# 02_ESP8266.net
KiCad netlist of a schematic drawn in Altium Designer
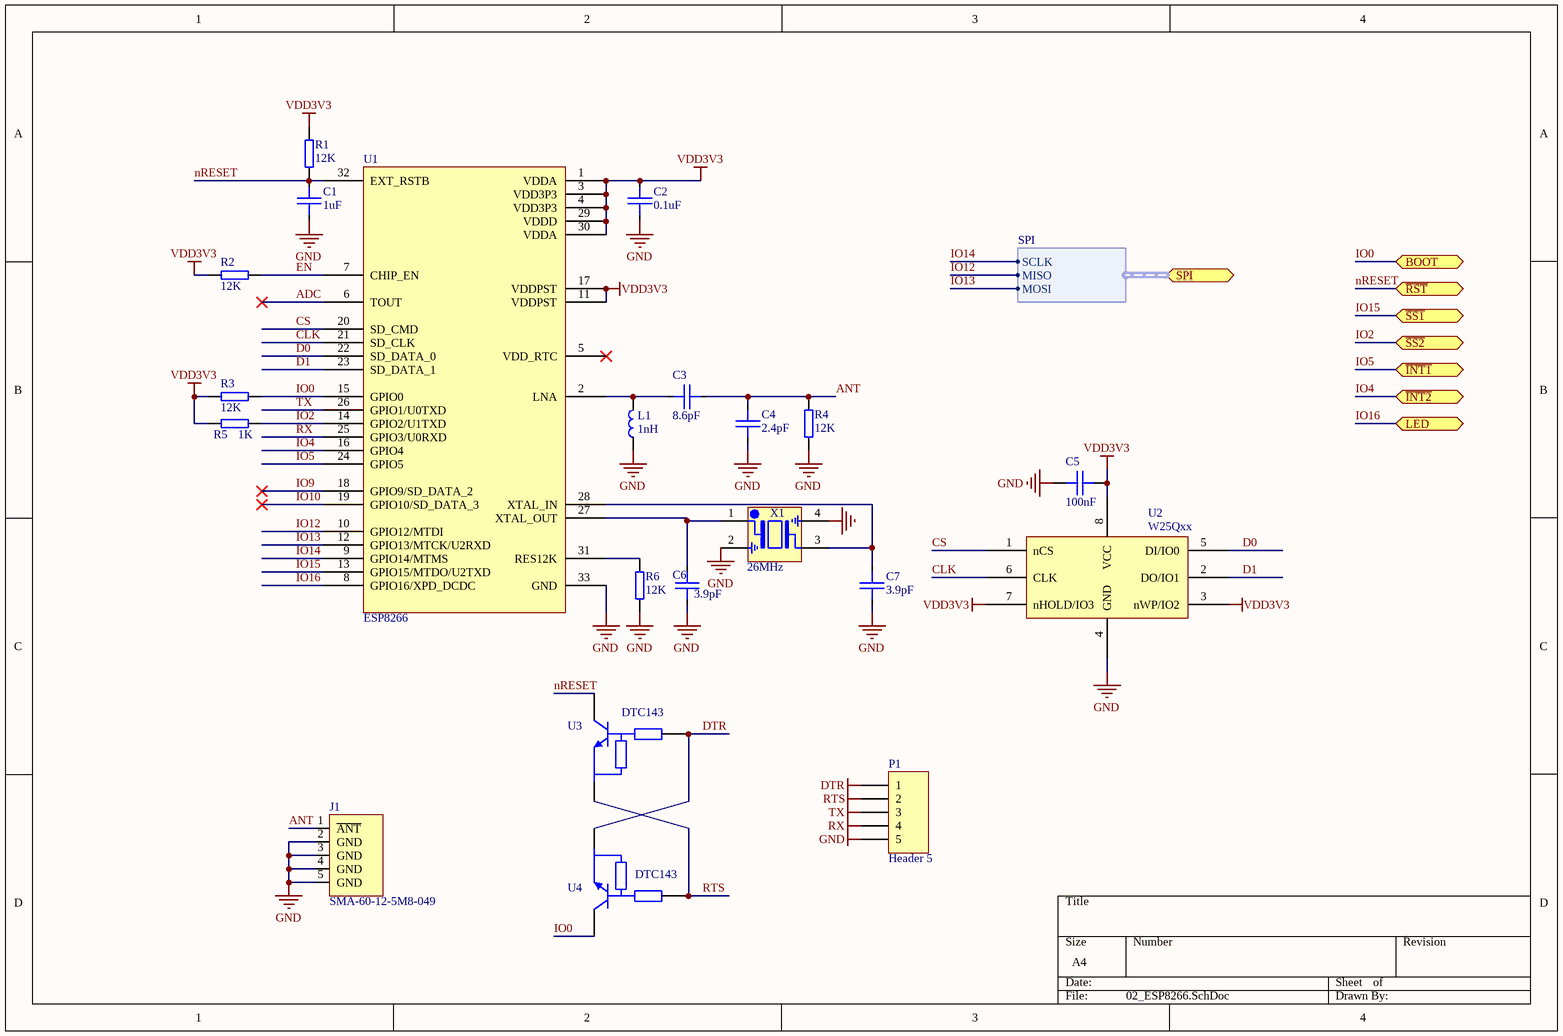
[diagram p0: 02_ESP8266.SchDoc]

(export (version "E")
  (design (tool "Eeschema 10.0.6"))
  (components
    (comp (ref "C1")
      (value "1uF")
      (footprint "SMT_C_0402")
      (description "Surface mount capacitor 0402")
      (libsource (lib "Vowstar_Basic_Device") (part "SMT_C_0402_1"))
    )
    (comp (ref "C2")
      (value "0.1uF")
      (footprint "SMT_C_0402")
      (description "Surface mount capacitor 0402")
      (libsource (lib "Vowstar_Basic_Device") (part "SMT_C_0402_1"))
    )
    (comp (ref "C3")
      (value "8.6pF")
      (footprint "SMT_C_0402")
      (description "Surface mount capacitor 0402")
      (libsource (lib "Vowstar_Basic_Device") (part "SMT_C_0402_1"))
    )
    (comp (ref "C4")
      (value "2.4pF")
      (footprint "SMT_C_0402")
      (description "Surface mount capacitor 0402")
      (libsource (lib "Vowstar_Basic_Device") (part "SMT_C_0402_1"))
    )
    (comp (ref "C5")
      (value "100nF")
      (footprint "SMT_C_0402")
      (description "Surface mount capacitor 0402")
      (libsource (lib "Vowstar_Basic_Device") (part "SMT_C_0402"))
    )
    (comp (ref "C6")
      (value "3.9pF")
      (footprint "SMT_C_0402")
      (description "Surface mount capacitor 0402")
      (libsource (lib "Vowstar_Basic_Device") (part "SMT_C_0402_1"))
    )
    (comp (ref "C7")
      (value "3.9pF")
      (footprint "SMT_C_0402")
      (description "Surface mount capacitor 0402")
      (libsource (lib "Vowstar_Basic_Device") (part "SMT_C_0402_1"))
    )
    (comp (ref "J1")
      (value "SMA-60-12-5M8-049")
      (footprint "SMA-60-12-5M8-049")
      (description "sma 60-12-5M8-049")
      (libsource (lib "Vowstar_Connector") (part "SMA-60-12-5M8-049"))
    )
    (comp (ref "L1")
      (value "1nH")
      (footprint "SMT_L_0402")
      (description "Surface mount inductor 0402")
      (libsource (lib "Vowstar_Basic_Device") (part "SMT_L_0402"))
    )
    (comp (ref "P1")
      (value "Header 5")
      (footprint "HDR1X5")
      (description "Header, 5-Pin")
      (fields (field (name "PUBLISHER") "Altium Limited"))
      (libsource (lib "Miscellaneous Connectors") (part "Header 5"))
    )
    (comp (ref "R1")
      (value "12K")
      (footprint "SMT_R_0402")
      (description "Surface mount resistor 0402")
      (libsource (lib "Vowstar_Basic_Device") (part "SMT_R_0402"))
    )
    (comp (ref "R2")
      (value "12K")
      (footprint "SMT_R_0402")
      (description "Surface mount resistor 0402")
      (libsource (lib "Vowstar_Basic_Device") (part "SMT_R_0402"))
    )
    (comp (ref "R3")
      (value "12K")
      (footprint "SMT_R_0402")
      (description "Surface mount resistor 0402")
      (libsource (lib "Vowstar_Basic_Device") (part "SMT_R_0402"))
    )
    (comp (ref "R4")
      (value "12K")
      (footprint "SMT_R_0402")
      (description "Surface mount resistor 0402")
      (libsource (lib "Vowstar_Basic_Device") (part "SMT_R_0402"))
    )
    (comp (ref "R5")
      (value "1K")
      (footprint "SMT_R_0402")
      (description "Surface mount resistor 0402")
      (libsource (lib "Vowstar_Basic_Device") (part "SMT_R_0402"))
    )
    (comp (ref "R6")
      (value "12K")
      (footprint "SMT_R_0402")
      (description "Surface mount resistor 0402")
      (libsource (lib "Vowstar_Basic_Device") (part "SMT_R_0402"))
    )
    (comp (ref "U1") (value "ESP8266") (footprint "QFN32") (libsource (lib "Vowstar_MCU") (part "ESP8266")))
    (comp (ref "U2")
      (value "W25Qxx")
      (footprint "SOP-8")
      (description "Serial flash memory with dual and quad SPI")
      (libsource (lib "Vowstar_IC_General") (part "W25Qxx"))
    )
    (comp (ref "U3")
      (value "DTC143")
      (footprint "SOT23-3")
      (description "Digital transistors (built-in resistors)")
      (libsource (lib "Vowstar_IC_General") (part "DTC143"))
    )
    (comp (ref "U4")
      (value "DTC143")
      (footprint "SOT23-3")
      (description "Digital transistors (built-in resistors)")
      (libsource (lib "Vowstar_IC_General") (part "DTC143"))
    )
    (comp (ref "X1")
      (value "26MHz")
      (footprint "SMT_XTAL_3225")
      (description "Passive crystal")
      (libsource (lib "Vowstar_Basic_Device") (part "SMT_XTAL_PASSIVE"))
    )
  )
  (nets
    (net (code "2") (name "/ADC") (class "Default")
      (node (ref "U1") (pin "6") (pinfunction "TOUT_6") (pintype "tri_state+no_connect"))
    )
    (net (code "3") (name "/ANT") (class "Default")
      (node (ref "C3") (pin "1") (pinfunction "1_1") (pintype "passive"))
      (node (ref "C4") (pin "1") (pinfunction "1_1") (pintype "passive"))
      (node (ref "J1") (pin "1") (pinfunction "~{ANT}_1") (pintype "passive"))
      (node (ref "R4") (pin "2") (pinfunction "2_2") (pintype "passive"))
    )
    (net (code "4") (name "/CLK") (class "Default")
      (node (ref "U1") (pin "21") (pinfunction "SD_CLK_21") (pintype "passive"))
      (node (ref "U2") (pin "6") (pinfunction "CLK_6") (pintype "passive"))
    )
    (net (code "5") (name "/CS") (class "Default")
      (node (ref "U1") (pin "20") (pinfunction "SD_CMD_20") (pintype "passive"))
      (node (ref "U2") (pin "1") (pinfunction "nCS_1") (pintype "passive"))
    )
    (net (code "6") (name "/D0") (class "Default")
      (node (ref "U1") (pin "22") (pinfunction "SD_DATA_0_22") (pintype "passive"))
      (node (ref "U2") (pin "5") (pinfunction "DI/IO0_5") (pintype "passive"))
    )
    (net (code "7") (name "/D1") (class "Default")
      (node (ref "U1") (pin "23") (pinfunction "SD_DATA_1_23") (pintype "passive"))
      (node (ref "U2") (pin "2") (pinfunction "DO/IO1_2") (pintype "passive"))
    )
    (net (code "8") (name "/EN") (class "Default")
      (node (ref "R2") (pin "1") (pinfunction "1_1") (pintype "passive"))
      (node (ref "U1") (pin "7") (pinfunction "CHIP_EN_7") (pintype "tri_state"))
    )
    (net (code "9") (name "/IO0") (class "Default")
      (node (ref "R3") (pin "1") (pinfunction "1_1") (pintype "passive"))
      (node (ref "U1") (pin "15") (pinfunction "GPIO0_15") (pintype "passive"))
      (node (ref "U4") (pin "3") (pinfunction "C_3") (pintype "passive"))
    )
    (net (code "10") (name "/IO2") (class "Default")
      (node (ref "R5") (pin "1") (pinfunction "1_1") (pintype "passive"))
      (node (ref "U1") (pin "14") (pinfunction "GPIO2/U1TXD_14") (pintype "passive"))
    )
    (net (code "11") (name "/IO4") (class "Default")
      (node (ref "U1") (pin "16") (pinfunction "GPIO4_16") (pintype "passive"))
    )
    (net (code "12") (name "/IO5") (class "Default")
      (node (ref "U1") (pin "24") (pinfunction "GPIO5_24") (pintype "passive"))
    )
    (net (code "13") (name "/IO9") (class "Default")
      (node (ref "U1") (pin "18") (pinfunction "GPIO9/SD_DATA_2_18") (pintype "passive+no_connect"))
    )
    (net (code "14") (name "/IO10") (class "Default")
      (node (ref "U1") (pin "19") (pinfunction "GPIO10/SD_DATA_3_19") (pintype "passive+no_connect"))
    )
    (net (code "15") (name "/IO12") (class "Default")
      (node (ref "U1") (pin "10") (pinfunction "GPIO12/MTDI_10") (pintype "passive"))
    )
    (net (code "16") (name "/IO13") (class "Default")
      (node (ref "U1") (pin "12") (pinfunction "GPIO13/MTCK/U2RXD_12") (pintype "passive"))
    )
    (net (code "17") (name "/IO14") (class "Default")
      (node (ref "U1") (pin "9") (pinfunction "GPIO14/MTMS_9") (pintype "passive"))
    )
    (net (code "18") (name "/IO15") (class "Default")
      (node (ref "U1") (pin "13") (pinfunction "GPIO15/MTDO/U2TXD_13") (pintype "passive"))
    )
    (net (code "19") (name "/IO16") (class "Default")
      (node (ref "U1") (pin "8") (pinfunction "GPIO16/XPD_DCDC_8") (pintype "passive"))
    )
    (net (code "20") (name "/nRESET") (class "Default")
      (node (ref "C1") (pin "1") (pinfunction "1_1") (pintype "passive"))
      (node (ref "R1") (pin "1") (pinfunction "1_1") (pintype "passive"))
      (node (ref "U1") (pin "32") (pinfunction "EXT_RSTB_32") (pintype "passive"))
      (node (ref "U3") (pin "3") (pinfunction "C_3") (pintype "passive"))
    )
    (net (code "22") (name "DTR") (class "Default")
      (node (ref "P1") (pin "1") (pinfunction "1_1") (pintype "passive"))
      (node (ref "U3") (pin "1") (pinfunction "B_1") (pintype "passive"))
      (node (ref "U4") (pin "2") (pinfunction "E_2") (pintype "passive"))
    )
    (net (code "23") (name "GND") (class "Default")
      (node (ref "C1") (pin "2") (pinfunction "2_2") (pintype "passive"))
      (node (ref "C2") (pin "2") (pinfunction "2_2") (pintype "passive"))
      (node (ref "C4") (pin "2") (pinfunction "2_2") (pintype "passive"))
      (node (ref "C5") (pin "2") (pinfunction "2_2") (pintype "passive"))
      (node (ref "C6") (pin "2") (pinfunction "2_2") (pintype "passive"))
      (node (ref "C7") (pin "2") (pinfunction "2_2") (pintype "passive"))
      (node (ref "J1") (pin "2") (pinfunction "GND_2") (pintype "passive"))
      (node (ref "J1") (pin "3") (pinfunction "GND_3") (pintype "passive"))
      (node (ref "J1") (pin "4") (pinfunction "GND_4") (pintype "passive"))
      (node (ref "J1") (pin "5") (pinfunction "GND_5") (pintype "passive"))
      (node (ref "L1") (pin "2") (pinfunction "2_2") (pintype "passive"))
      (node (ref "P1") (pin "5") (pinfunction "5_5") (pintype "passive"))
      (node (ref "R4") (pin "1") (pinfunction "1_1") (pintype "passive"))
      (node (ref "R6") (pin "2") (pinfunction "2_2") (pintype "passive"))
      (node (ref "U1") (pin "33") (pinfunction "GND_33") (pintype "power_in"))
      (node (ref "U2") (pin "4") (pinfunction "GND_4") (pintype "passive"))
      (node (ref "X1") (pin "2") (pinfunction "GND_2") (pintype "passive"))
      (node (ref "X1") (pin "4") (pinfunction "GND_4") (pintype "passive"))
    )
    (net (code "24") (name "Net-(U1-LNA)") (class "Default")
      (node (ref "C3") (pin "2") (pinfunction "2_2") (pintype "passive"))
      (node (ref "L1") (pin "1") (pinfunction "1_1") (pintype "passive"))
      (node (ref "U1") (pin "2") (pinfunction "LNA_2") (pintype "tri_state"))
    )
    (net (code "25") (name "Net-(U1-RES12K)") (class "Default")
      (node (ref "R6") (pin "1") (pinfunction "1_1") (pintype "passive"))
      (node (ref "U1") (pin "31") (pinfunction "RES12K_31") (pintype "passive"))
    )
    (net (code "26") (name "Net-(U1-XTAL_IN)") (class "Default")
      (node (ref "C7") (pin "1") (pinfunction "1_1") (pintype "passive"))
      (node (ref "U1") (pin "28") (pinfunction "XTAL_IN_28") (pintype "passive"))
      (node (ref "X1") (pin "3") (pinfunction "IN/OUT_3") (pintype "passive"))
    )
    (net (code "27") (name "Net-(U1-XTAL_OUT)") (class "Default")
      (node (ref "C6") (pin "1") (pinfunction "1_1") (pintype "passive"))
      (node (ref "U1") (pin "27") (pinfunction "XTAL_OUT_27") (pintype "passive"))
      (node (ref "X1") (pin "1") (pinfunction "IN/OUT_1") (pintype "passive"))
    )
    (net (code "28") (name "RTS") (class "Default")
      (node (ref "P1") (pin "2") (pinfunction "2_2") (pintype "passive"))
      (node (ref "U3") (pin "2") (pinfunction "E_2") (pintype "passive"))
      (node (ref "U4") (pin "1") (pinfunction "B_1") (pintype "passive"))
    )
    (net (code "29") (name "RX") (class "Default")
      (node (ref "P1") (pin "4") (pinfunction "4_4") (pintype "passive"))
      (node (ref "U1") (pin "25") (pinfunction "GPIO3/U0RXD_25") (pintype "passive"))
    )
    (net (code "30") (name "TX") (class "Default")
      (node (ref "P1") (pin "3") (pinfunction "3_3") (pintype "passive"))
      (node (ref "U1") (pin "26") (pinfunction "GPIO1/U0TXD_26") (pintype "passive"))
    )
    (net (code "31") (name "VDD3V3") (class "Default")
      (node (ref "C2") (pin "1") (pinfunction "1_1") (pintype "passive"))
      (node (ref "C5") (pin "1") (pinfunction "1_1") (pintype "passive"))
      (node (ref "R1") (pin "2") (pinfunction "2_2") (pintype "passive"))
      (node (ref "R2") (pin "2") (pinfunction "2_2") (pintype "passive"))
      (node (ref "R3") (pin "2") (pinfunction "2_2") (pintype "passive"))
      (node (ref "R5") (pin "2") (pinfunction "2_2") (pintype "passive"))
      (node (ref "U1") (pin "1") (pinfunction "VDDA_1") (pintype "power_in"))
      (node (ref "U1") (pin "11") (pinfunction "VDDPST_11") (pintype "power_in"))
      (node (ref "U1") (pin "17") (pinfunction "VDDPST_17") (pintype "power_in"))
      (node (ref "U1") (pin "29") (pinfunction "VDDD_29") (pintype "power_in"))
      (node (ref "U1") (pin "3") (pinfunction "VDD3P3_3") (pintype "power_in"))
      (node (ref "U1") (pin "30") (pinfunction "VDDA_30") (pintype "power_in"))
      (node (ref "U1") (pin "4") (pinfunction "VDD3P3_4") (pintype "power_in"))
      (node (ref "U2") (pin "3") (pinfunction "nWP/IO2_3") (pintype "passive"))
      (node (ref "U2") (pin "7") (pinfunction "nHOLD/IO3_7") (pintype "passive"))
      (node (ref "U2") (pin "8") (pinfunction "VCC_8") (pintype "passive"))
    )
    (net (code "32") (name "unconnected-(U1-VDD_RTC-Pad5)") (class "Default")
      (node (ref "U1") (pin "5") (pinfunction "VDD_RTC_5") (pintype "power_in+no_connect"))
    )
  )
)
